# Mozard.net
KiCad netlist of a schematic drawn in EAGLE
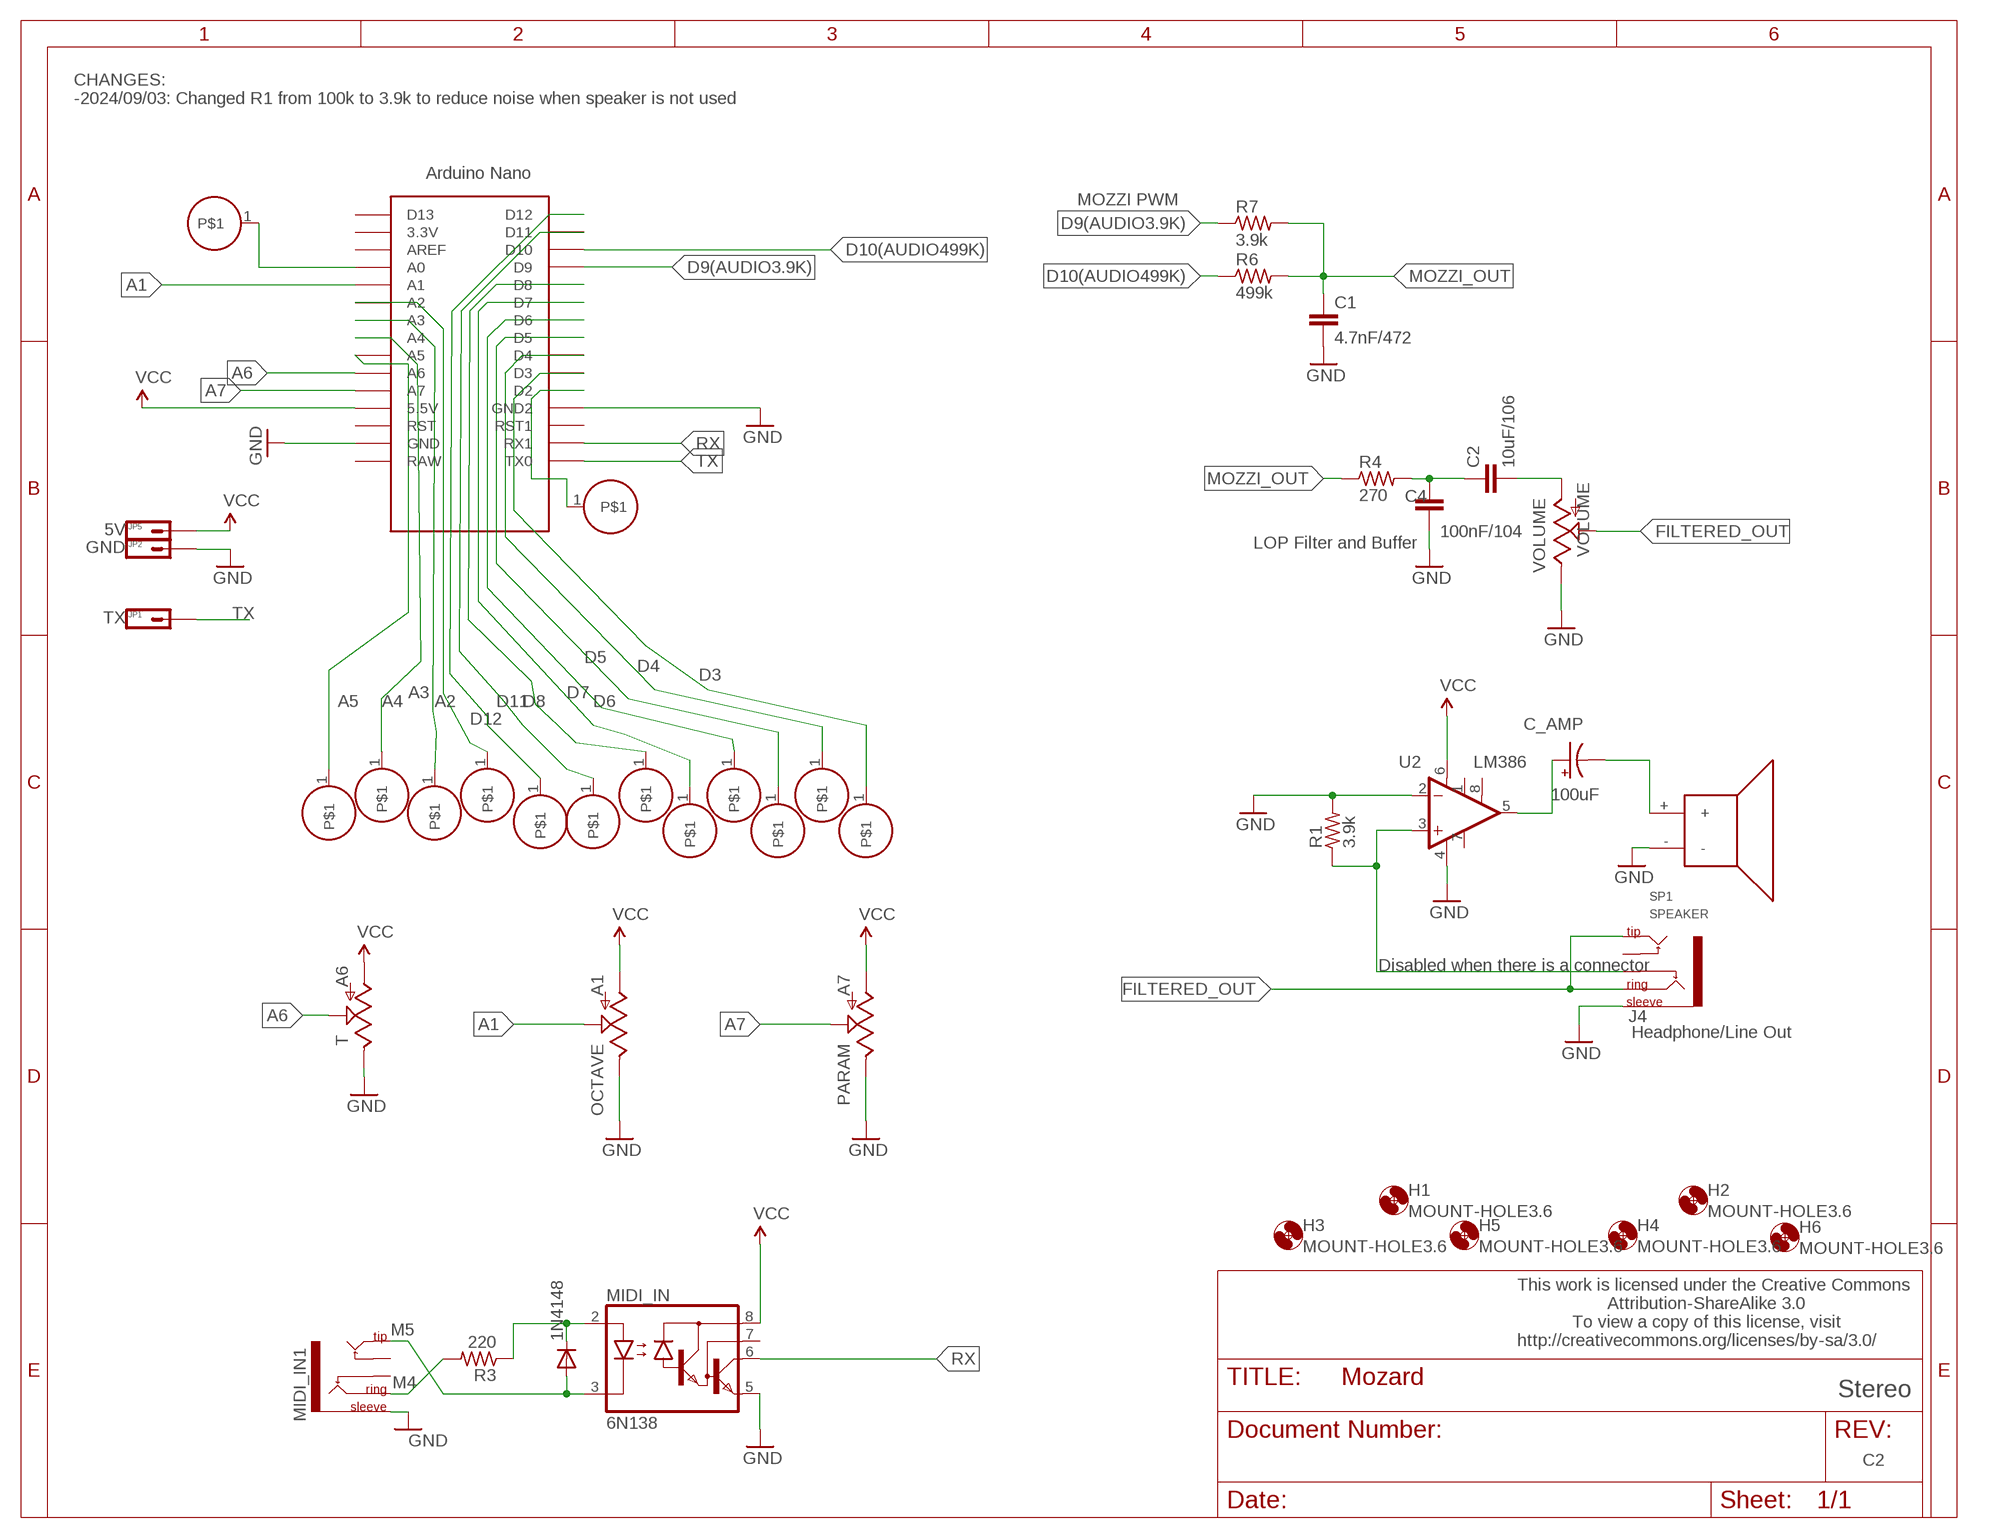
[diagram p0: schematic, sheet 1]

(export (version "E")
  (design (tool "Eeschema 10.0.6"))
  (components
    (comp (ref "1N4148")
      (value "1N4148")
      (footprint "eagle-import:DO41-10")
      (libsource (lib "eagle-import") (part "DIODE"))
    )
    (comp (ref "C1")
      (value "4.7nF/472")
      (footprint "eagle-import:CAP-PTH-SMALL-KIT")
      (libsource (lib "eagle-import") (part "0.1UF-50V-20%(PTH)KIT-EZ"))
    )
    (comp (ref "C2")
      (value "10uF/106")
      (footprint "eagle-import:CAP-PTH-SMALL-KIT")
      (libsource (lib "eagle-import") (part "0.1UF-50V-20%(PTH)KIT-EZ"))
    )
    (comp (ref "C4")
      (value "100nF/104")
      (footprint "eagle-import:CAP-PTH-SMALL-KIT")
      (libsource (lib "eagle-import") (part "0.1UF-50V-20%(PTH)KIT-EZ"))
    )
    (comp (ref "C_AMP")
      (value "100uF")
      (footprint "eagle-import:CPOL-RADIAL-10UF-25V")
      (libsource (lib "eagle-import") (part "CPOL-RADIAL-10UF-25V"))
    )
    (comp (ref "H1")
      (value "MOUNT-HOLE3.6")
      (footprint "eagle-import:3,6")
      (libsource (lib "eagle-import") (part "MOUNT-HOLE3.6"))
    )
    (comp (ref "H2")
      (value "MOUNT-HOLE3.6")
      (footprint "eagle-import:3,6")
      (libsource (lib "eagle-import") (part "MOUNT-HOLE3.6"))
    )
    (comp (ref "H3")
      (value "MOUNT-HOLE3.6")
      (footprint "eagle-import:3,6")
      (libsource (lib "eagle-import") (part "MOUNT-HOLE3.6"))
    )
    (comp (ref "H4")
      (value "MOUNT-HOLE3.6")
      (footprint "eagle-import:3,6")
      (libsource (lib "eagle-import") (part "MOUNT-HOLE3.6"))
    )
    (comp (ref "H5")
      (value "MOUNT-HOLE3.6")
      (footprint "eagle-import:3,6")
      (libsource (lib "eagle-import") (part "MOUNT-HOLE3.6"))
    )
    (comp (ref "H6")
      (value "MOUNT-HOLE3.6")
      (footprint "eagle-import:3,6")
      (libsource (lib "eagle-import") (part "MOUNT-HOLE3.6"))
    )
    (comp (ref "J4")
      (value "Headphone/Line Out")
      (footprint "eagle-import:AUDIO-JACK")
      (libsource (lib "eagle-import") (part "AUDIO-JACKPTH"))
    )
    (comp (ref "JP1")
      (value "TX")
      (footprint "eagle-import:1X01_SIDE_NAME")
      (libsource (lib "eagle-import") (part "HEADER-1X1"))
    )
    (comp (ref "JP2")
      (value "GND")
      (footprint "eagle-import:1X01_SIDE_NAME")
      (libsource (lib "eagle-import") (part "HEADER-1X1"))
    )
    (comp (ref "JP5")
      (value "5V")
      (footprint "eagle-import:1X01_SIDE_NAME")
      (libsource (lib "eagle-import") (part "HEADER-1X1"))
    )
    (comp (ref "MIDI_IN")
      (value "6N138")
      (footprint "eagle-import:DIL08")
      (fields (field (name "MF") "VISHAY/TELEFUNKEN"))
      (libsource (lib "eagle-import") (part "6N138"))
    )
    (comp (ref "MIDI_IN1")
      (value "AUDIO-JACKKIT")
      (footprint "eagle-import:AUDIO-JACK-KIT")
      (libsource (lib "eagle-import") (part "AUDIO-JACKKIT"))
    )
    (comp (ref "OCTAVE")
      (value "A1")
      (footprint "eagle-import:ALPS_POT")
      (libsource (lib "eagle-import") (part "POT"))
    )
    (comp (ref "PARAM")
      (value "A7")
      (footprint "eagle-import:ALPS_POT")
      (libsource (lib "eagle-import") (part "POT"))
    )
    (comp (ref "R1")
      (value "3.9k")
      (footprint "eagle-import:0204_7")
      (libsource (lib "eagle-import") (part "R-US_0204/7"))
    )
    (comp (ref "R3")
      (value "220")
      (footprint "eagle-import:0204_5")
      (libsource (lib "eagle-import") (part "R-US_0204/5"))
    )
    (comp (ref "R4")
      (value "270")
      (footprint "eagle-import:0204_7")
      (libsource (lib "eagle-import") (part "R-US_0204/7"))
    )
    (comp (ref "R6")
      (value "499k")
      (footprint "eagle-import:0204_7")
      (libsource (lib "eagle-import") (part "R-US_0204/7"))
    )
    (comp (ref "R7")
      (value "3.9k")
      (footprint "eagle-import:0204_7")
      (libsource (lib "eagle-import") (part "R-US_0204/7"))
    )
    (comp (ref "SP1")
      (value "SPEAKER")
      (footprint "eagle-import:PCB_MOUNT_SPEAKER")
      (fields (field (name "MFG") "SANCO"))
      (libsource (lib "eagle-import") (part "SPEAKERPCB_MOUNT"))
    )
    (comp (ref "T")
      (value "A6")
      (footprint "eagle-import:ALPS_POT")
      (libsource (lib "eagle-import") (part "POT"))
    )
    (comp (ref "U$1")
      (value "NANO")
      (footprint "eagle-import:NANO")
      (libsource (lib "eagle-import") (part "NANO"))
    )
    (comp (ref "U$2")
      (value "PCB-TOUCHPAD-1-PIN")
      (footprint "eagle-import:PCB-TOUCHPAD-1-PIN")
      (libsource (lib "eagle-import") (part "PCB-TOUCHPAD-1-PIN"))
    )
    (comp (ref "U$3")
      (value "PCB-TOUCHPAD-1-PIN")
      (footprint "eagle-import:PCB-TOUCHPAD-1-PIN")
      (libsource (lib "eagle-import") (part "PCB-TOUCHPAD-1-PIN"))
    )
    (comp (ref "U$4")
      (value "PCB-TOUCHPAD-1-PIN")
      (footprint "eagle-import:PCB-TOUCHPAD-1-PIN")
      (libsource (lib "eagle-import") (part "PCB-TOUCHPAD-1-PIN"))
    )
    (comp (ref "U$5")
      (value "PCB-TOUCHPAD-1-PIN")
      (footprint "eagle-import:PCB-TOUCHPAD-1-PIN")
      (libsource (lib "eagle-import") (part "PCB-TOUCHPAD-1-PIN"))
    )
    (comp (ref "U$6")
      (value "PCB-TOUCHPAD-1-PIN")
      (footprint "eagle-import:PCB-TOUCHPAD-1-PIN")
      (libsource (lib "eagle-import") (part "PCB-TOUCHPAD-1-PIN"))
    )
    (comp (ref "U$7")
      (value "PCB-TOUCHPAD-1-PIN")
      (footprint "eagle-import:PCB-TOUCHPAD-1-PIN")
      (libsource (lib "eagle-import") (part "PCB-TOUCHPAD-1-PIN"))
    )
    (comp (ref "U$8")
      (value "PCB-TOUCHPAD-1-PIN")
      (footprint "eagle-import:PCB-TOUCHPAD-1-PIN")
      (libsource (lib "eagle-import") (part "PCB-TOUCHPAD-1-PIN"))
    )
    (comp (ref "U$9")
      (value "PCB-TOUCHPAD-1-PIN")
      (footprint "eagle-import:PCB-TOUCHPAD-1-PIN")
      (libsource (lib "eagle-import") (part "PCB-TOUCHPAD-1-PIN"))
    )
    (comp (ref "U$10")
      (value "PCB-TOUCHPAD-1-PIN")
      (footprint "eagle-import:PCB-TOUCHPAD-1-PIN")
      (libsource (lib "eagle-import") (part "PCB-TOUCHPAD-1-PIN"))
    )
    (comp (ref "U$11")
      (value "PCB-TOUCHPAD-1-PIN")
      (footprint "eagle-import:PCB-TOUCHPAD-1-PIN")
      (libsource (lib "eagle-import") (part "PCB-TOUCHPAD-1-PIN"))
    )
    (comp (ref "U$12")
      (value "PCB-TOUCHPAD-1-PIN")
      (footprint "eagle-import:PCB-TOUCHPAD-1-PIN")
      (libsource (lib "eagle-import") (part "PCB-TOUCHPAD-1-PIN"))
    )
    (comp (ref "U$13")
      (value "PCB-TOUCHPAD-1-PIN")
      (footprint "eagle-import:PCB-TOUCHPAD-1-PIN")
      (libsource (lib "eagle-import") (part "PCB-TOUCHPAD-1-PIN"))
    )
    (comp (ref "U$14")
      (value "PCB-TOUCHPAD-1-PIN")
      (footprint "eagle-import:PCB-TOUCHPAD-1-PIN")
      (libsource (lib "eagle-import") (part "PCB-TOUCHPAD-1-PIN"))
    )
    (comp (ref "U$15")
      (value "PCB-TOUCHPAD-1-PIN")
      (footprint "eagle-import:PCB-TOUCHPAD-1-PIN")
      (libsource (lib "eagle-import") (part "PCB-TOUCHPAD-1-PIN"))
    )
    (comp (ref "U2")
      (value "LM386")
      (footprint "eagle-import:DIP08")
      (libsource (lib "eagle-import") (part "LM386"))
    )
    (comp (ref "VOLUME")
      (value "VOLUME")
      (footprint "eagle-import:ALPS_POT")
      (libsource (lib "eagle-import") (part "POT"))
    )
  )
  (nets
    (net (code "1") (name "/A2") (class "Default")
      (node (ref "U$1") (pin "A2") (pinfunction "A2_A2") (pintype "bidirectional"))
      (node (ref "U$5") (pin "1") (pinfunction "P$1_1") (pintype "bidirectional"))
    )
    (net (code "2") (name "/A3") (class "Default")
      (node (ref "U$1") (pin "A3") (pinfunction "A3_A3") (pintype "bidirectional"))
      (node (ref "U$4") (pin "1") (pinfunction "P$1_1") (pintype "bidirectional"))
    )
    (net (code "3") (name "/A4") (class "Default")
      (node (ref "U$1") (pin "A4") (pinfunction "A4_A4") (pintype "bidirectional"))
      (node (ref "U$3") (pin "1") (pinfunction "P$1_1") (pintype "bidirectional"))
    )
    (net (code "4") (name "/A5") (class "Default")
      (node (ref "U$1") (pin "A5") (pinfunction "A5_A5") (pintype "bidirectional"))
      (node (ref "U$2") (pin "1") (pinfunction "P$1_1") (pintype "bidirectional"))
    )
    (net (code "5") (name "/D3") (class "Default")
      (node (ref "U$1") (pin "D3") (pinfunction "D3_D3") (pintype "bidirectional"))
      (node (ref "U$13") (pin "1") (pinfunction "P$1_1") (pintype "bidirectional"))
    )
    (net (code "6") (name "/D4") (class "Default")
      (node (ref "U$1") (pin "D4") (pinfunction "D4_D4") (pintype "bidirectional"))
      (node (ref "U$12") (pin "1") (pinfunction "P$1_1") (pintype "bidirectional"))
    )
    (net (code "7") (name "/D5") (class "Default")
      (node (ref "U$1") (pin "D5") (pinfunction "D5_D5") (pintype "bidirectional"))
      (node (ref "U$11") (pin "1") (pinfunction "P$1_1") (pintype "bidirectional"))
    )
    (net (code "8") (name "/D6") (class "Default")
      (node (ref "U$1") (pin "D6") (pinfunction "D6_D6") (pintype "bidirectional"))
      (node (ref "U$10") (pin "1") (pinfunction "P$1_1") (pintype "bidirectional"))
    )
    (net (code "9") (name "/D7") (class "Default")
      (node (ref "U$1") (pin "D7") (pinfunction "D7_D7") (pintype "bidirectional"))
      (node (ref "U$9") (pin "1") (pinfunction "P$1_1") (pintype "bidirectional"))
    )
    (net (code "10") (name "/D8") (class "Default")
      (node (ref "U$1") (pin "D8") (pinfunction "D8_D8") (pintype "bidirectional"))
      (node (ref "U$8") (pin "1") (pinfunction "P$1_1") (pintype "bidirectional"))
    )
    (net (code "11") (name "/D11") (class "Default")
      (node (ref "U$1") (pin "D11") (pinfunction "D11_D11") (pintype "bidirectional"))
      (node (ref "U$7") (pin "1") (pinfunction "P$1_1") (pintype "bidirectional"))
    )
    (net (code "12") (name "/D12") (class "Default")
      (node (ref "U$1") (pin "D12") (pinfunction "D12_D12") (pintype "bidirectional"))
      (node (ref "U$6") (pin "1") (pinfunction "P$1_1") (pintype "bidirectional"))
    )
    (net (code "13") (name "/M4") (class "Default")
      (node (ref "MIDI_IN1") (pin "RING") (pinfunction "RING_RING") (pintype "bidirectional"))
      (node (ref "R3") (pin "2") (pinfunction "2_2") (pintype "passive"))
    )
    (net (code "14") (name "/M5") (class "Default")
      (node (ref "1N4148") (pin "A") (pinfunction "A_A") (pintype "passive"))
      (node (ref "MIDI_IN") (pin "3") (pinfunction "C_3") (pintype "passive"))
      (node (ref "MIDI_IN1") (pin "TIP") (pinfunction "TIP_TIP") (pintype "bidirectional"))
    )
    (net (code "15") (name "A1") (class "Default")
      (node (ref "OCTAVE") (pin "P$2") (pinfunction "S_P$2") (pintype "passive"))
      (node (ref "U$1") (pin "A1") (pinfunction "A1_A1") (pintype "bidirectional"))
    )
    (net (code "16") (name "A6") (class "Default")
      (node (ref "T") (pin "P$2") (pinfunction "S_P$2") (pintype "passive"))
      (node (ref "U$1") (pin "A6") (pinfunction "A6_A6") (pintype "bidirectional"))
    )
    (net (code "17") (name "A7") (class "Default")
      (node (ref "PARAM") (pin "P$2") (pinfunction "S_P$2") (pintype "passive"))
      (node (ref "U$1") (pin "A7") (pinfunction "A7_A7") (pintype "bidirectional"))
    )
    (net (code "18") (name "D9(AUDIO3.9K)") (class "Default")
      (node (ref "R7") (pin "1") (pinfunction "1_1") (pintype "passive"))
      (node (ref "U$1") (pin "D9") (pinfunction "D9_D9") (pintype "bidirectional"))
    )
    (net (code "19") (name "D10(AUDIO499K)") (class "Default")
      (node (ref "R6") (pin "1") (pinfunction "1_1") (pintype "passive"))
      (node (ref "U$1") (pin "D10") (pinfunction "D10_D10") (pintype "bidirectional"))
    )
    (net (code "20") (name "FILTERED_OUT") (class "Default")
      (node (ref "J4") (pin "RING") (pinfunction "RING_RING") (pintype "bidirectional"))
      (node (ref "J4") (pin "TIP") (pinfunction "TIP_TIP") (pintype "bidirectional"))
      (node (ref "VOLUME") (pin "P$2") (pinfunction "S_P$2") (pintype "passive"))
    )
    (net (code "21") (name "GND") (class "Default")
      (node (ref "C1") (pin "2") (pinfunction "2_2") (pintype "passive"))
      (node (ref "C4") (pin "2") (pinfunction "2_2") (pintype "passive"))
      (node (ref "J4") (pin "SLEEVE") (pinfunction "SLEEVE_SLEEVE") (pintype "bidirectional"))
      (node (ref "JP2") (pin "1") (pinfunction "1_1") (pintype "passive"))
      (node (ref "MIDI_IN") (pin "5") (pinfunction "GND_5") (pintype "passive"))
      (node (ref "MIDI_IN1") (pin "SLEEVE") (pinfunction "SLEEVE_SLEEVE") (pintype "bidirectional"))
      (node (ref "OCTAVE") (pin "P$1") (pinfunction "E_P$1") (pintype "passive"))
      (node (ref "PARAM") (pin "P$1") (pinfunction "E_P$1") (pintype "passive"))
      (node (ref "R1") (pin "2") (pinfunction "2_2") (pintype "passive"))
      (node (ref "SP1") (pin "-") (pinfunction "-_-") (pintype "bidirectional"))
      (node (ref "T") (pin "P$1") (pinfunction "E_P$1") (pintype "passive"))
      (node (ref "U$1") (pin "GND") (pinfunction "GND_GND") (pintype "bidirectional"))
      (node (ref "U$1") (pin "GND1") (pinfunction "GND2_GND1") (pintype "bidirectional"))
      (node (ref "U2") (pin "2") (pinfunction "-IN_2") (pintype "input"))
      (node (ref "U2") (pin "4") (pinfunction "V-_4") (pintype "power_in"))
      (node (ref "VOLUME") (pin "P$1") (pinfunction "E_P$1") (pintype "passive"))
    )
    (net (code "22") (name "MOZZI_OUT") (class "Default")
      (node (ref "C1") (pin "1") (pinfunction "1_1") (pintype "passive"))
      (node (ref "R4") (pin "1") (pinfunction "1_1") (pintype "passive"))
      (node (ref "R6") (pin "2") (pinfunction "2_2") (pintype "passive"))
      (node (ref "R7") (pin "2") (pinfunction "2_2") (pintype "passive"))
    )
    (net (code "23") (name "Net-(C2-Pad1)") (class "Default")
      (node (ref "C2") (pin "1") (pinfunction "1_1") (pintype "passive"))
      (node (ref "C4") (pin "1") (pinfunction "1_1") (pintype "passive"))
      (node (ref "R4") (pin "2") (pinfunction "2_2") (pintype "passive"))
    )
    (net (code "24") (name "Net-(C_AMP-Pad-)") (class "Default")
      (node (ref "C_AMP") (pin "-") (pinfunction "-_-") (pintype "passive"))
      (node (ref "SP1") (pin "+") (pinfunction "+_+") (pintype "bidirectional"))
    )
    (net (code "25") (name "Net-(MIDI_IN-A)") (class "Default")
      (node (ref "1N4148") (pin "C") (pinfunction "C_C") (pintype "passive"))
      (node (ref "MIDI_IN") (pin "2") (pinfunction "A_2") (pintype "passive"))
      (node (ref "R3") (pin "1") (pinfunction "1_1") (pintype "passive"))
    )
    (net (code "26") (name "Net-(U$14-P$1)") (class "Default")
      (node (ref "U$1") (pin "D2") (pinfunction "D2_D2") (pintype "bidirectional"))
      (node (ref "U$14") (pin "1") (pinfunction "P$1_1") (pintype "bidirectional"))
    )
    (net (code "27") (name "Net-(U$15-P$1)") (class "Default")
      (node (ref "U$1") (pin "A0") (pinfunction "A0_A0") (pintype "bidirectional"))
      (node (ref "U$15") (pin "1") (pinfunction "P$1_1") (pintype "bidirectional"))
    )
    (net (code "28") (name "Net-(U2-+IN)") (class "Default")
      (node (ref "J4") (pin "RSH") (pinfunction "RSH_RSH") (pintype "bidirectional"))
      (node (ref "R1") (pin "1") (pinfunction "1_1") (pintype "passive"))
      (node (ref "U2") (pin "3") (pinfunction "+IN_3") (pintype "input"))
    )
    (net (code "29") (name "Net-(U2-OUT)") (class "Default")
      (node (ref "C_AMP") (pin "+") (pinfunction "+_+") (pintype "passive"))
      (node (ref "U2") (pin "5") (pinfunction "OUT_5") (pintype "output"))
    )
    (net (code "30") (name "Net-(VOLUME-A)") (class "Default")
      (node (ref "C2") (pin "2") (pinfunction "2_2") (pintype "passive"))
      (node (ref "VOLUME") (pin "P$3") (pinfunction "A_P$3") (pintype "passive"))
    )
    (net (code "31") (name "RX") (class "Default")
      (node (ref "MIDI_IN") (pin "6") (pinfunction "VO_6") (pintype "passive"))
      (node (ref "U$1") (pin "RX1") (pinfunction "RX1_RX1") (pintype "bidirectional"))
    )
    (net (code "32") (name "TX") (class "Default")
      (node (ref "JP1") (pin "1") (pinfunction "1_1") (pintype "passive"))
      (node (ref "U$1") (pin "TX0") (pinfunction "TX0_TX0") (pintype "bidirectional"))
    )
    (net (code "33") (name "VCC") (class "Default")
      (node (ref "JP5") (pin "1") (pinfunction "1_1") (pintype "passive"))
      (node (ref "MIDI_IN") (pin "8") (pinfunction "VCC_8") (pintype "passive"))
      (node (ref "OCTAVE") (pin "P$3") (pinfunction "A_P$3") (pintype "passive"))
      (node (ref "PARAM") (pin "P$3") (pinfunction "A_P$3") (pintype "passive"))
      (node (ref "T") (pin "P$3") (pinfunction "A_P$3") (pintype "passive"))
      (node (ref "U$1") (pin "5V") (pinfunction "5.5V_5V") (pintype "bidirectional"))
      (node (ref "U2") (pin "6") (pinfunction "V+_6") (pintype "power_in"))
    )
    (net (code "34") (name "unconnected-(J4-PadTSH)") (class "Default")
      (node (ref "J4") (pin "TSH") (pinfunction "TSH_TSH") (pintype "bidirectional"))
    )
    (net (code "35") (name "unconnected-(MIDI_IN-VB-Pad7)") (class "Default")
      (node (ref "MIDI_IN") (pin "7") (pinfunction "VB_7") (pintype "passive"))
    )
    (net (code "36") (name "unconnected-(MIDI_IN1-PadRSH)") (class "Default")
      (node (ref "MIDI_IN1") (pin "RSH") (pinfunction "RSH_RSH") (pintype "bidirectional"))
    )
    (net (code "37") (name "unconnected-(MIDI_IN1-PadTSH)") (class "Default")
      (node (ref "MIDI_IN1") (pin "TSH") (pinfunction "TSH_TSH") (pintype "bidirectional"))
    )
    (net (code "38") (name "unconnected-(U$1-Pad3.3V)") (class "Default")
      (node (ref "U$1") (pin "3.3V") (pinfunction "3.3V_3.3V") (pintype "bidirectional"))
    )
    (net (code "39") (name "unconnected-(U$1-PadAREF)") (class "Default")
      (node (ref "U$1") (pin "AREF") (pinfunction "AREF_AREF") (pintype "bidirectional"))
    )
    (net (code "40") (name "unconnected-(U$1-PadD13)") (class "Default")
      (node (ref "U$1") (pin "D13") (pinfunction "D13_D13") (pintype "bidirectional"))
    )
    (net (code "41") (name "unconnected-(U$1-PadRAW)") (class "Default")
      (node (ref "U$1") (pin "RAW") (pinfunction "RAW_RAW") (pintype "bidirectional"))
    )
    (net (code "42") (name "unconnected-(U$1-PadRST)") (class "Default")
      (node (ref "U$1") (pin "RST") (pinfunction "RST_RST") (pintype "bidirectional"))
    )
    (net (code "43") (name "unconnected-(U$1-PadRST1)") (class "Default")
      (node (ref "U$1") (pin "RST1") (pinfunction "RST1_RST1") (pintype "bidirectional"))
    )
    (net (code "44") (name "unconnected-(U2-BP-Pad7)") (class "Default")
      (node (ref "U2") (pin "7") (pinfunction "BP_7") (pintype "bidirectional"))
    )
    (net (code "45") (name "unconnected-(U2-GAIN-Pad1)") (class "Default")
      (node (ref "U2") (pin "1") (pinfunction "GAIN_1") (pintype "bidirectional"))
    )
    (net (code "46") (name "unconnected-(U2-GAIN-Pad8)") (class "Default")
      (node (ref "U2") (pin "8") (pinfunction "GAIN_8") (pintype "bidirectional"))
    )
  )
)
